# Open_tES.net
KiCad netlist of a schematic drawn in EAGLE
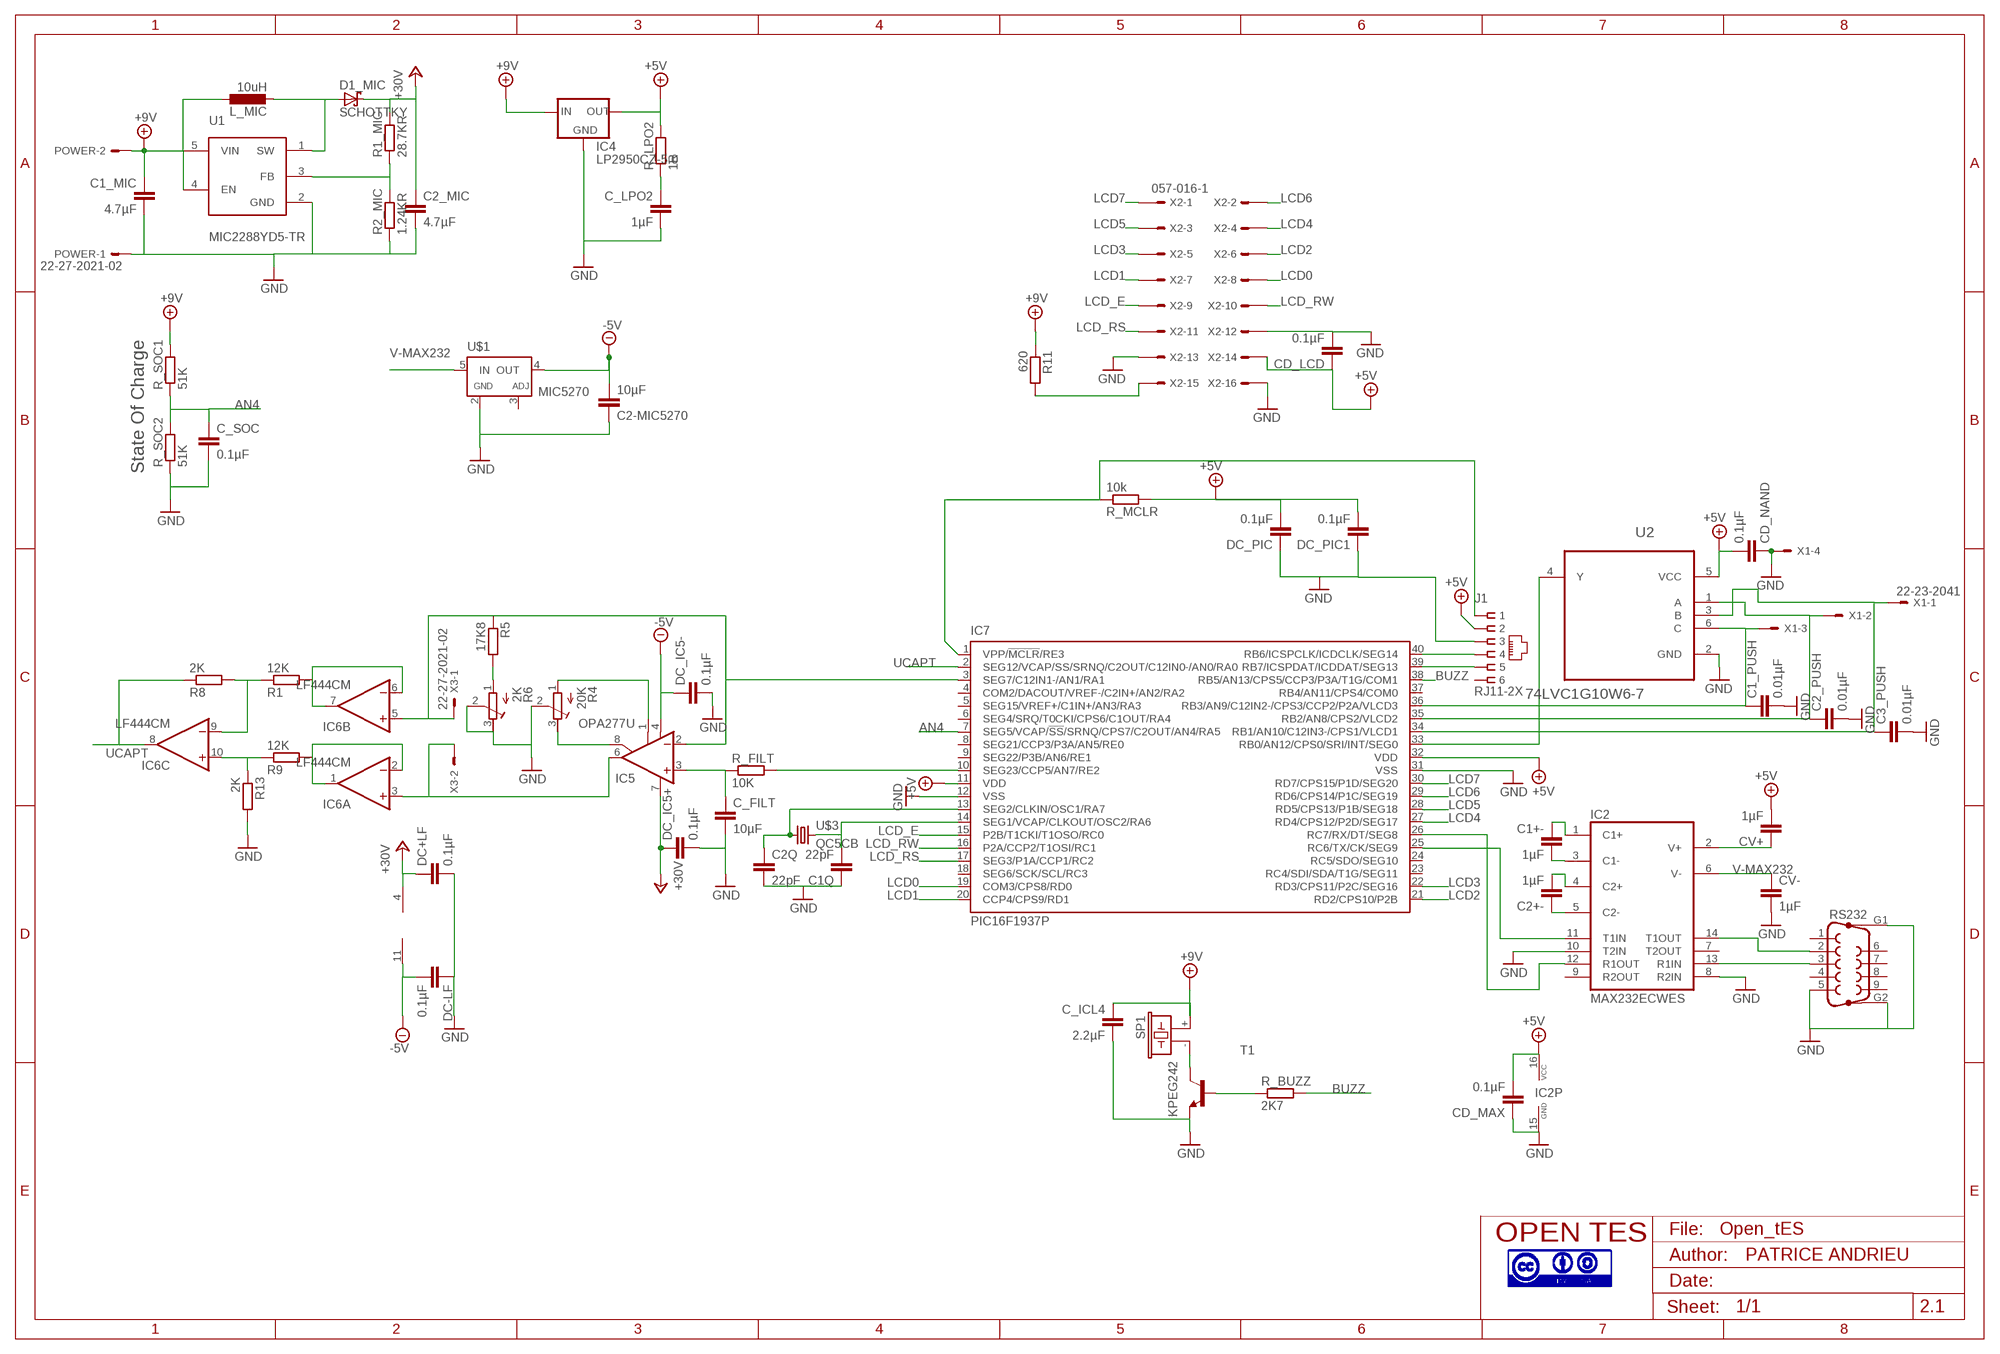
[diagram p0: schematic, sheet 1]

(export (version "E")
  (design (tool "Eeschema 10.0.6"))
  (components
    (comp (ref "C1+-")
      (value "1µF")
      (footprint "eagle-import:C0805")
      (libsource (lib "eagle-import") (part "C-EUC0805"))
    )
    (comp (ref "C1Q")
      (value "22pF")
      (footprint "eagle-import:C0805")
      (libsource (lib "eagle-import") (part "C-EUC0805"))
    )
    (comp (ref "C1_MIC")
      (value "4.7µF")
      (footprint "eagle-import:C0805")
      (libsource (lib "eagle-import") (part "C-EUC0805"))
    )
    (comp (ref "C1_PUSH")
      (value "0.01µF")
      (footprint "eagle-import:C0805")
      (libsource (lib "eagle-import") (part "C-EUC0805"))
    )
    (comp (ref "C2+-")
      (value "1µF")
      (footprint "eagle-import:C0805")
      (libsource (lib "eagle-import") (part "C-EUC0805"))
    )
    (comp (ref "C2-MIC5270")
      (value "10µF")
      (footprint "eagle-import:C0805")
      (libsource (lib "eagle-import") (part "C-EUC0805"))
    )
    (comp (ref "C2Q")
      (value "22pF")
      (footprint "eagle-import:C0805")
      (libsource (lib "eagle-import") (part "C-EUC0805"))
    )
    (comp (ref "C2_MIC")
      (value "4.7µF")
      (footprint "eagle-import:C0805")
      (libsource (lib "eagle-import") (part "C-EUC0805"))
    )
    (comp (ref "C2_PUSH")
      (value "0.01µF")
      (footprint "eagle-import:C0805")
      (libsource (lib "eagle-import") (part "C-EUC0805"))
    )
    (comp (ref "C3_PUSH")
      (value "0.01µF")
      (footprint "eagle-import:C0805")
      (libsource (lib "eagle-import") (part "C-EUC0805"))
    )
    (comp (ref "CD_LCD")
      (value "0.1µF")
      (footprint "eagle-import:C0805")
      (libsource (lib "eagle-import") (part "C-EUC0805"))
    )
    (comp (ref "CD_MAX")
      (value "0.1µF")
      (footprint "eagle-import:C0805")
      (libsource (lib "eagle-import") (part "C-EUC0805"))
    )
    (comp (ref "CD_NAND")
      (value "0.1µF")
      (footprint "eagle-import:C0805")
      (libsource (lib "eagle-import") (part "C-EUC0805"))
    )
    (comp (ref "CV+")
      (value "1µF")
      (footprint "eagle-import:C0805")
      (libsource (lib "eagle-import") (part "C-EUC0805"))
    )
    (comp (ref "CV-")
      (value "1µF")
      (footprint "eagle-import:C0805")
      (libsource (lib "eagle-import") (part "C-EUC0805"))
    )
    (comp (ref "C_FILT")
      (value "10µF")
      (footprint "eagle-import:C0805")
      (libsource (lib "eagle-import") (part "C-EUC0805"))
    )
    (comp (ref "C_ICL4")
      (value "2.2µF")
      (footprint "eagle-import:C0805K")
      (libsource (lib "eagle-import") (part "C-EUC0805K"))
    )
    (comp (ref "C_LPO2")
      (value "1µF")
      (footprint "eagle-import:C0805")
      (libsource (lib "eagle-import") (part "C-EUC0805"))
    )
    (comp (ref "C_SOC")
      (value "0.1µF")
      (footprint "eagle-import:C0805")
      (libsource (lib "eagle-import") (part "C-EUC0805"))
    )
    (comp (ref "D1_MIC")
      (value "SCHOTTKY")
      (footprint "eagle-import:SOD80")
      (libsource (lib "eagle-import") (part "SCHOTTKY"))
    )
    (comp (ref "DC+LF")
      (value "0.1µF")
      (footprint "eagle-import:C0805")
      (libsource (lib "eagle-import") (part "C-EUC0805"))
    )
    (comp (ref "DC-LF")
      (value "0.1µF")
      (footprint "eagle-import:C0805")
      (libsource (lib "eagle-import") (part "C-EUC0805"))
    )
    (comp (ref "DC_IC5+")
      (value "0.1µF")
      (footprint "eagle-import:C0805")
      (libsource (lib "eagle-import") (part "C-EUC0805"))
    )
    (comp (ref "DC_IC5-")
      (value "0.1µF")
      (footprint "eagle-import:C0805")
      (libsource (lib "eagle-import") (part "C-EUC0805"))
    )
    (comp (ref "DC_PIC")
      (value "0.1µF")
      (footprint "eagle-import:C0805")
      (libsource (lib "eagle-import") (part "C-EUC0805"))
    )
    (comp (ref "DC_PIC1")
      (value "0.1µF")
      (footprint "eagle-import:C0805")
      (libsource (lib "eagle-import") (part "C-EUC0805"))
    )
    (comp (ref "IC2")
      (value "MAX232ECWES")
      (footprint "eagle-import:SO16")
      (fields (field (name "OC_FARNELL") "2511968"))
      (libsource (lib "eagle-import") (part "MAX232ECWES"))
    )
    (comp (ref "IC4")
      (value "LP2950CZ-5.0")
      (footprint "eagle-import:TO92")
      (libsource (lib "eagle-import") (part "LP2950?CZ-5.0"))
    )
    (comp (ref "IC5")
      (value "OPA277U")
      (footprint "eagle-import:SO08")
      (libsource (lib "eagle-import") (part "OPA277U"))
    )
    (comp (ref "IC6")
      (value "LF444CM")
      (footprint "eagle-import:SO14")
      (fields (field (name "OC_FARNELL") "1564711"))
      (libsource (lib "eagle-import") (part "LF444CM"))
    )
    (comp (ref "IC7")
      (value "PIC16F1937P")
      (footprint "eagle-import:DIL40")
      (fields (field (name "MPN") "PIC16F1937-I/P"))
      (libsource (lib "eagle-import") (part "PIC16F193?P7"))
    )
    (comp (ref "J1")
      (value "RJ11-2X")
      (footprint "eagle-import:RJ11-NO_SHIELD")
      (fields (field (name "OC_FARNELL") "3363132"))
      (libsource (lib "eagle-import") (part "RJ11-2X"))
    )
    (comp (ref "L_MIC")
      (value "10uH")
      (footprint "eagle-import:L2012C")
      (libsource (lib "eagle-import") (part "L-EUL2012C"))
    )
    (comp (ref "POWER")
      (value "22-27-2021-02")
      (footprint "eagle-import:6410-02")
      (fields (field (name "OC_FARNELL") "9731148+1654528+1462641"))
      (libsource (lib "eagle-import") (part "22-?-0227-2021"))
    )
    (comp (ref "R1")
      (value "12K")
      (footprint "eagle-import:R0805")
      (libsource (lib "eagle-import") (part "R-EU_R0805"))
    )
    (comp (ref "R1_MIC")
      (value "28.7KR")
      (footprint "eagle-import:R0805")
      (libsource (lib "eagle-import") (part "R-EU_R0805"))
    )
    (comp (ref "R2_MIC")
      (value "1.24KR")
      (footprint "eagle-import:R0805")
      (libsource (lib "eagle-import") (part "R-EU_R0805"))
    )
    (comp (ref "R4")
      (value "20K")
      (footprint "eagle-import:RTRIM3214W")
      (libsource (lib "eagle-import") (part "R-TRIMM3214W"))
    )
    (comp (ref "R5")
      (value "17K8")
      (footprint "eagle-import:M0805")
      (libsource (lib "eagle-import") (part "R-EU_M0805"))
    )
    (comp (ref "R6")
      (value "2K")
      (footprint "eagle-import:RTRIM3214W")
      (libsource (lib "eagle-import") (part "R-TRIMM3214W"))
    )
    (comp (ref "R8")
      (value "2K")
      (footprint "eagle-import:R0805")
      (libsource (lib "eagle-import") (part "R-EU_R0805"))
    )
    (comp (ref "R9")
      (value "12K")
      (footprint "eagle-import:R0805")
      (libsource (lib "eagle-import") (part "R-EU_R0805"))
    )
    (comp (ref "R11")
      (value "620")
      (footprint "eagle-import:0204_7")
      (libsource (lib "eagle-import") (part "R-EU_0204/7"))
    )
    (comp (ref "R13")
      (value "2K")
      (footprint "eagle-import:R0805")
      (libsource (lib "eagle-import") (part "R-EU_R0805"))
    )
    (comp (ref "RS232")
      (value "F09HP")
      (footprint "eagle-import:F09HP")
      (fields (field (name "OC_FARNELL") "1084701"))
      (libsource (lib "eagle-import") (part "F09HP"))
    )
    (comp (ref "R_BUZZ")
      (value "2K7")
      (footprint "eagle-import:R0805")
      (libsource (lib "eagle-import") (part "R-EU_R0805"))
    )
    (comp (ref "R_FILT")
      (value "10K")
      (footprint "eagle-import:R0805")
      (libsource (lib "eagle-import") (part "R-EU_R0805"))
    )
    (comp (ref "R_LPO2")
      (value "1R")
      (footprint "eagle-import:R0805")
      (libsource (lib "eagle-import") (part "R-EU_R0805"))
    )
    (comp (ref "R_MCLR")
      (value "10k")
      (footprint "eagle-import:0204_7")
      (libsource (lib "eagle-import") (part "R-EU_0204/7"))
    )
    (comp (ref "R_SOC1")
      (value "51K")
      (footprint "eagle-import:R0805")
      (libsource (lib "eagle-import") (part "R-EU_R0805"))
    )
    (comp (ref "R_SOC2")
      (value "51K")
      (footprint "eagle-import:R0805")
      (libsource (lib "eagle-import") (part "R-EU_R0805"))
    )
    (comp (ref "SP1")
      (value "KPEG242")
      (footprint "eagle-import:KPEG242")
      (fields (field (name "OC_FARNELL") "1502726"))
      (libsource (lib "eagle-import") (part "KPEG242"))
    )
    (comp (ref "T1")
      (value "BFR92-NPN-SOT23-BEC")
      (footprint "eagle-import:SOT23-BEC")
      (libsource (lib "eagle-import") (part "-NPN-SOT23-BECBFR92"))
    )
    (comp (ref "U$1")
      (value "MIC5270")
      (footprint "eagle-import:SOT23-5L")
      (libsource (lib "eagle-import") (part "MIC5270"))
    )
    (comp (ref "U$3")
      (value "QC5CB")
      (footprint "eagle-import:QC5CB")
      (libsource (lib "eagle-import") (part "QC5CB"))
    )
    (comp (ref "U$4")
      (value "FRAME")
      (footprint "eagle-import:OPEN_TE_VERSION")
      (fields (field (name "VERSION") "2.1"))
      (libsource (lib "eagle-import") (part "FRAME"))
    )
    (comp (ref "U1")
      (value "MIC2288YD5-TR")
      (footprint "eagle-import:SOT23-5L")
      (libsource (lib "eagle-import") (part "MIC2288YD5-TR"))
    )
    (comp (ref "U2")
      (value "74LVC1G10W6-7")
      (footprint "eagle-import:SOT95P280X135-6N")
      (libsource (lib "eagle-import") (part "74LVC1G10W6-7"))
    )
    (comp (ref "X1")
      (value "22-23-2041")
      (footprint "eagle-import:22-23-2041")
      (fields (field (name "MF") "MOLEX") (field (name "OC_FARNELL") "1462920+1462809+1462641"))
      (libsource (lib "eagle-import") (part "22-23-2041"))
    )
    (comp (ref "X2")
      (value "057-016-1")
      (footprint "eagle-import:057-016-1")
      (fields (field (name "OC_FARNELL") "1554029"))
      (libsource (lib "eagle-import") (part "057-016-1"))
    )
    (comp (ref "X3")
      (value "22-27-2021-02")
      (footprint "eagle-import:6410-02")
      (fields (field (name "OC_FARNELL") "9731148+1654528+1462641"))
      (libsource (lib "eagle-import") (part "22-?-0227-2021"))
    )
  )
  (nets
    (net (code "1") (name "+5V") (class "Default")
      (node (ref "CD_LCD") (pin "1") (pinfunction "1_1") (pintype "passive"))
      (node (ref "CD_MAX") (pin "2") (pinfunction "2_2") (pintype "passive"))
      (node (ref "CD_NAND") (pin "2") (pinfunction "2_2") (pintype "passive"))
      (node (ref "CV+") (pin "2") (pinfunction "2_2") (pintype "passive"))
      (node (ref "DC_PIC") (pin "2") (pinfunction "2_2") (pintype "passive"))
      (node (ref "DC_PIC1") (pin "2") (pinfunction "2_2") (pintype "passive"))
      (node (ref "IC2") (pin "16") (pinfunction "VCC_16") (pintype "power_in"))
      (node (ref "IC4") (pin "1") (pinfunction "OUT_1") (pintype "passive"))
      (node (ref "IC7") (pin "11") (pinfunction "VDD_11") (pintype "power_in"))
      (node (ref "IC7") (pin "32") (pinfunction "VDD_32") (pintype "power_in"))
      (node (ref "J1") (pin "2") (pinfunction "2_2") (pintype "passive"))
      (node (ref "R_LPO2") (pin "2") (pinfunction "2_2") (pintype "passive"))
      (node (ref "R_MCLR") (pin "2") (pinfunction "2_2") (pintype "passive"))
      (node (ref "U2") (pin "5") (pinfunction "VCC_5") (pintype "power_in"))
      (node (ref "X2") (pin "14") (pinfunction "S_14") (pintype "passive"))
    )
    (net (code "2") (name "+9V") (class "Default")
      (node (ref "C1_MIC") (pin "1") (pinfunction "1_1") (pintype "passive"))
      (node (ref "C_ICL4") (pin "1") (pinfunction "1_1") (pintype "passive"))
      (node (ref "IC4") (pin "3") (pinfunction "IN_3") (pintype "input"))
      (node (ref "L_MIC") (pin "1") (pinfunction "1_1") (pintype "passive"))
      (node (ref "POWER") (pin "2") (pinfunction "S_2") (pintype "passive"))
      (node (ref "R11") (pin "1") (pinfunction "1_1") (pintype "passive"))
      (node (ref "R_SOC1") (pin "2") (pinfunction "2_2") (pintype "passive"))
      (node (ref "SP1") (pin "+") (pinfunction "1_+") (pintype "passive"))
      (node (ref "U1") (pin "4") (pinfunction "EN_4") (pintype "bidirectional"))
      (node (ref "U1") (pin "5") (pinfunction "VIN_5") (pintype "bidirectional"))
    )
    (net (code "3") (name "+30V") (class "Default")
      (node (ref "C2_MIC") (pin "1") (pinfunction "1_1") (pintype "passive"))
      (node (ref "D1_MIC") (pin "C") (pinfunction "C_C") (pintype "passive"))
      (node (ref "DC+LF") (pin "1") (pinfunction "1_1") (pintype "passive"))
      (node (ref "DC_IC5+") (pin "1") (pinfunction "1_1") (pintype "passive"))
      (node (ref "IC5") (pin "7") (pinfunction "V+_7") (pintype "power_in"))
      (node (ref "IC6") (pin "4") (pinfunction "V+_4") (pintype "power_in"))
      (node (ref "R1_MIC") (pin "2") (pinfunction "2_2") (pintype "passive"))
    )
    (net (code "4") (name "-5V") (class "Default")
      (node (ref "C2-MIC5270") (pin "2") (pinfunction "2_2") (pintype "passive"))
      (node (ref "DC-LF") (pin "2") (pinfunction "2_2") (pintype "passive"))
      (node (ref "DC_IC5-") (pin "1") (pinfunction "1_1") (pintype "passive"))
      (node (ref "IC5") (pin "4") (pinfunction "V-_4") (pintype "power_in"))
      (node (ref "IC6") (pin "11") (pinfunction "V-_11") (pintype "power_in"))
      (node (ref "U$1") (pin "4") (pinfunction "OUT_4") (pintype "output"))
    )
    (net (code "5") (name "/AN4") (class "Default")
      (node (ref "C_SOC") (pin "1") (pinfunction "1_1") (pintype "passive"))
      (node (ref "IC7") (pin "7") (pinfunction "SEG5/VCAP/~{SS}/SRNQ/CPS7/C2OUT/AN4/RA5_7") (pintype "bidirectional"))
      (node (ref "R_SOC1") (pin "1") (pinfunction "1_1") (pintype "passive"))
      (node (ref "R_SOC2") (pin "2") (pinfunction "2_2") (pintype "passive"))
    )
    (net (code "6") (name "/BUZZ") (class "Default")
      (node (ref "IC7") (pin "38") (pinfunction "RB5/AN13/CPS5/CCP3/P3A/T1G/COM1_38") (pintype "bidirectional"))
      (node (ref "R_BUZZ") (pin "2") (pinfunction "2_2") (pintype "passive"))
    )
    (net (code "7") (name "/LCD0") (class "Default")
      (node (ref "IC7") (pin "19") (pinfunction "COM3/CPS8/RD0_19") (pintype "bidirectional"))
      (node (ref "X2") (pin "8") (pinfunction "S_8") (pintype "passive"))
    )
    (net (code "8") (name "/LCD1") (class "Default")
      (node (ref "IC7") (pin "20") (pinfunction "CCP4/CPS9/RD1_20") (pintype "bidirectional"))
      (node (ref "X2") (pin "7") (pinfunction "S_7") (pintype "passive"))
    )
    (net (code "9") (name "/LCD2") (class "Default")
      (node (ref "IC7") (pin "21") (pinfunction "RD2/CPS10/P2B_21") (pintype "bidirectional"))
      (node (ref "X2") (pin "6") (pinfunction "S_6") (pintype "passive"))
    )
    (net (code "10") (name "/LCD3") (class "Default")
      (node (ref "IC7") (pin "22") (pinfunction "RD3/CPS11/P2C/SEG16_22") (pintype "bidirectional"))
      (node (ref "X2") (pin "5") (pinfunction "S_5") (pintype "passive"))
    )
    (net (code "11") (name "/LCD4") (class "Default")
      (node (ref "IC7") (pin "27") (pinfunction "RD4/CPS12/P2D/SEG17_27") (pintype "bidirectional"))
      (node (ref "X2") (pin "4") (pinfunction "S_4") (pintype "passive"))
    )
    (net (code "12") (name "/LCD5") (class "Default")
      (node (ref "IC7") (pin "28") (pinfunction "RD5/CPS13/P1B/SEG18_28") (pintype "bidirectional"))
      (node (ref "X2") (pin "3") (pinfunction "S_3") (pintype "passive"))
    )
    (net (code "13") (name "/LCD6") (class "Default")
      (node (ref "IC7") (pin "29") (pinfunction "RD6/CPS14/P1C/SEG19_29") (pintype "bidirectional"))
      (node (ref "X2") (pin "2") (pinfunction "S_2") (pintype "passive"))
    )
    (net (code "14") (name "/LCD7") (class "Default")
      (node (ref "IC7") (pin "30") (pinfunction "RD7/CPS15/P1D/SEG20_30") (pintype "bidirectional"))
      (node (ref "X2") (pin "1") (pinfunction "S_1") (pintype "passive"))
    )
    (net (code "15") (name "/LCD_E") (class "Default")
      (node (ref "IC7") (pin "15") (pinfunction "P2B/T1CKI/T1OSO/RC0_15") (pintype "bidirectional"))
      (node (ref "X2") (pin "9") (pinfunction "S_9") (pintype "passive"))
    )
    (net (code "16") (name "/LCD_RS") (class "Default")
      (node (ref "IC7") (pin "17") (pinfunction "SEG3/P1A/CCP1/RC2_17") (pintype "bidirectional"))
      (node (ref "X2") (pin "11") (pinfunction "S_11") (pintype "passive"))
    )
    (net (code "17") (name "/LCD_RW") (class "Default")
      (node (ref "IC7") (pin "16") (pinfunction "P2A/CCP2/T1OSI/RC1_16") (pintype "bidirectional"))
      (node (ref "X2") (pin "10") (pinfunction "S_10") (pintype "passive"))
    )
    (net (code "18") (name "/UCAPT") (class "Default")
      (node (ref "IC6") (pin "8") (pinfunction "OUT_8") (pintype "output"))
      (node (ref "IC7") (pin "2") (pinfunction "SEG12/VCAP/SS/SRNQ/C2OUT/C12IN0-/AN0/RA0_2") (pintype "bidirectional"))
      (node (ref "R8") (pin "1") (pinfunction "1_1") (pintype "passive"))
    )
    (net (code "19") (name "/V-MAX232") (class "Default")
      (node (ref "CV-") (pin "1") (pinfunction "1_1") (pintype "passive"))
      (node (ref "IC2") (pin "6") (pinfunction "V-_6") (pintype "bidirectional"))
      (node (ref "U$1") (pin "5") (pinfunction "IN_5") (pintype "input"))
    )
    (net (code "20") (name "GND") (class "Default")
      (node (ref "C1Q") (pin "1") (pinfunction "1_1") (pintype "passive"))
      (node (ref "C1_MIC") (pin "2") (pinfunction "2_2") (pintype "passive"))
      (node (ref "C1_PUSH") (pin "2") (pinfunction "2_2") (pintype "passive"))
      (node (ref "C2-MIC5270") (pin "1") (pinfunction "1_1") (pintype "passive"))
      (node (ref "C2Q") (pin "2") (pinfunction "2_2") (pintype "passive"))
      (node (ref "C2_MIC") (pin "2") (pinfunction "2_2") (pintype "passive"))
      (node (ref "C2_PUSH") (pin "2") (pinfunction "2_2") (pintype "passive"))
      (node (ref "C3_PUSH") (pin "2") (pinfunction "2_2") (pintype "passive"))
      (node (ref "CD_LCD") (pin "2") (pinfunction "2_2") (pintype "passive"))
      (node (ref "CD_MAX") (pin "1") (pinfunction "1_1") (pintype "passive"))
      (node (ref "CD_NAND") (pin "1") (pinfunction "1_1") (pintype "passive"))
      (node (ref "CV-") (pin "2") (pinfunction "2_2") (pintype "passive"))
      (node (ref "C_FILT") (pin "2") (pinfunction "2_2") (pintype "passive"))
      (node (ref "C_ICL4") (pin "2") (pinfunction "2_2") (pintype "passive"))
      (node (ref "C_LPO2") (pin "2") (pinfunction "2_2") (pintype "passive"))
      (node (ref "C_SOC") (pin "2") (pinfunction "2_2") (pintype "passive"))
      (node (ref "DC+LF") (pin "2") (pinfunction "2_2") (pintype "passive"))
      (node (ref "DC-LF") (pin "1") (pinfunction "1_1") (pintype "passive"))
      (node (ref "DC_IC5+") (pin "2") (pinfunction "2_2") (pintype "passive"))
      (node (ref "DC_IC5-") (pin "2") (pinfunction "2_2") (pintype "passive"))
      (node (ref "DC_PIC") (pin "1") (pinfunction "1_1") (pintype "passive"))
      (node (ref "DC_PIC1") (pin "1") (pinfunction "1_1") (pintype "passive"))
      (node (ref "IC2") (pin "10") (pinfunction "T2IN_10") (pintype "input"))
      (node (ref "IC2") (pin "15") (pinfunction "GND_15") (pintype "power_in"))
      (node (ref "IC2") (pin "8") (pinfunction "R2IN_8") (pintype "input"))
      (node (ref "IC4") (pin "2") (pinfunction "GND_2") (pintype "input"))
      (node (ref "IC7") (pin "12") (pinfunction "VSS_12") (pintype "power_in"))
      (node (ref "IC7") (pin "31") (pinfunction "VSS_31") (pintype "power_in"))
      (node (ref "J1") (pin "3") (pinfunction "3_3") (pintype "passive"))
      (node (ref "POWER") (pin "1") (pinfunction "S_1") (pintype "passive"))
      (node (ref "R13") (pin "2") (pinfunction "2_2") (pintype "passive"))
      (node (ref "R2_MIC") (pin "1") (pinfunction "1_1") (pintype "passive"))
      (node (ref "R4") (pin "2") (pinfunction "S_2") (pintype "passive"))
      (node (ref "R6") (pin "2") (pinfunction "S_2") (pintype "passive"))
      (node (ref "R6") (pin "3") (pinfunction "E_3") (pintype "passive"))
      (node (ref "RS232") (pin "5") (pinfunction "5_5") (pintype "passive"))
      (node (ref "RS232") (pin "G1") (pinfunction "G1_G1") (pintype "passive"))
      (node (ref "RS232") (pin "G2") (pinfunction "G2_G2") (pintype "passive"))
      (node (ref "R_SOC2") (pin "1") (pinfunction "1_1") (pintype "passive"))
      (node (ref "T1") (pin "E") (pinfunction "E_E") (pintype "passive"))
      (node (ref "U$1") (pin "2") (pinfunction "GND_2") (pintype "power_in"))
      (node (ref "U1") (pin "2") (pinfunction "GND_2") (pintype "bidirectional"))
      (node (ref "U2") (pin "2") (pinfunction "GND_2") (pintype "passive"))
      (node (ref "X1") (pin "4") (pinfunction "S_4") (pintype "passive"))
      (node (ref "X2") (pin "12") (pinfunction "S_12") (pintype "passive"))
      (node (ref "X2") (pin "13") (pinfunction "S_13") (pintype "passive"))
      (node (ref "X2") (pin "16") (pinfunction "S_16") (pintype "passive"))
    )
    (net (code "21") (name "Net-(C_LPO2-Pad1)") (class "Default")
      (node (ref "C_LPO2") (pin "1") (pinfunction "1_1") (pintype "passive"))
      (node (ref "R_LPO2") (pin "1") (pinfunction "1_1") (pintype "passive"))
    )
    (net (code "22") (name "Net-(IC2A-C1+)") (class "Default")
      (node (ref "C1+-") (pin "1") (pinfunction "1_1") (pintype "passive"))
      (node (ref "IC2") (pin "1") (pinfunction "C1+_1") (pintype "bidirectional"))
    )
    (net (code "23") (name "Net-(IC2A-C1-)") (class "Default")
      (node (ref "C1+-") (pin "2") (pinfunction "2_2") (pintype "passive"))
      (node (ref "IC2") (pin "3") (pinfunction "C1-_3") (pintype "bidirectional"))
    )
    (net (code "24") (name "Net-(IC2A-C2+)") (class "Default")
      (node (ref "C2+-") (pin "2") (pinfunction "2_2") (pintype "passive"))
      (node (ref "IC2") (pin "4") (pinfunction "C2+_4") (pintype "bidirectional"))
    )
    (net (code "25") (name "Net-(IC2A-C2-)") (class "Default")
      (node (ref "C2+-") (pin "1") (pinfunction "1_1") (pintype "passive"))
      (node (ref "IC2") (pin "5") (pinfunction "C2-_5") (pintype "bidirectional"))
    )
    (net (code "26") (name "Net-(IC2A-R1IN)") (class "Default")
      (node (ref "IC2") (pin "13") (pinfunction "R1IN_13") (pintype "input"))
      (node (ref "RS232") (pin "3") (pinfunction "3_3") (pintype "passive"))
    )
    (net (code "27") (name "Net-(IC2A-R1OUT)") (class "Default")
      (node (ref "IC2") (pin "12") (pinfunction "R1OUT_12") (pintype "output"))
      (node (ref "IC7") (pin "26") (pinfunction "RC7/RX/DT/SEG8_26") (pintype "bidirectional"))
    )
    (net (code "28") (name "Net-(IC2A-T1IN)") (class "Default")
      (node (ref "IC2") (pin "11") (pinfunction "T1IN_11") (pintype "input"))
      (node (ref "IC7") (pin "25") (pinfunction "RC6/TX/CK/SEG9_25") (pintype "bidirectional"))
    )
    (net (code "29") (name "Net-(IC2A-T1OUT)") (class "Default")
      (node (ref "IC2") (pin "14") (pinfunction "T1OUT_14") (pintype "output"))
      (node (ref "RS232") (pin "2") (pinfunction "2_2") (pintype "passive"))
    )
    (net (code "30") (name "Net-(IC2A-V+)") (class "Default")
      (node (ref "CV+") (pin "1") (pinfunction "1_1") (pintype "passive"))
      (node (ref "IC2") (pin "2") (pinfunction "V+_2") (pintype "bidirectional"))
    )
    (net (code "31") (name "Net-(IC5-+IN)") (class "Default")
      (node (ref "C_FILT") (pin "1") (pinfunction "1_1") (pintype "passive"))
      (node (ref "IC5") (pin "3") (pinfunction "+IN_3") (pintype "input"))
      (node (ref "R_FILT") (pin "1") (pinfunction "1_1") (pintype "passive"))
    )
    (net (code "32") (name "Net-(IC5--IN)") (class "Default")
      (node (ref "IC5") (pin "2") (pinfunction "-IN_2") (pintype "input"))
      (node (ref "IC6") (pin "5") (pinfunction "+IN_5") (pintype "input"))
      (node (ref "IC7") (pin "3") (pinfunction "SEG7/C12IN1-/AN1/RA1_3") (pintype "bidirectional"))
      (node (ref "R5") (pin "1") (pinfunction "1_1") (pintype "passive"))
      (node (ref "X3") (pin "1") (pinfunction "S_1") (pintype "passive"))
    )
    (net (code "33") (name "Net-(IC5-CMP1)") (class "Default")
      (node (ref "IC5") (pin "1") (pinfunction "CMP1_1") (pintype "passive"))
      (node (ref "R4") (pin "1") (pinfunction "A_1") (pintype "passive"))
    )
    (net (code "34") (name "Net-(IC5-CMP2)") (class "Default")
      (node (ref "IC5") (pin "8") (pinfunction "CMP2_8") (pintype "passive"))
      (node (ref "R4") (pin "3") (pinfunction "E_3") (pintype "passive"))
    )
    (net (code "35") (name "Net-(IC5-OUT)") (class "Default")
      (node (ref "IC5") (pin "6") (pinfunction "OUT_6") (pintype "output"))
      (node (ref "IC6") (pin "3") (pinfunction "+IN_3") (pintype "input"))
      (node (ref "X3") (pin "2") (pinfunction "S_2") (pintype "passive"))
    )
    (net (code "36") (name "Net-(IC6A--IN)") (class "Default")
      (node (ref "IC6") (pin "1") (pinfunction "OUT_1") (pintype "output"))
      (node (ref "IC6") (pin "2") (pinfunction "-IN_2") (pintype "input"))
      (node (ref "R9") (pin "2") (pinfunction "2_2") (pintype "passive"))
    )
    (net (code "37") (name "Net-(IC6B--IN)") (class "Default")
      (node (ref "IC6") (pin "6") (pinfunction "-IN_6") (pintype "input"))
      (node (ref "IC6") (pin "7") (pinfunction "OUT_7") (pintype "output"))
      (node (ref "R1") (pin "2") (pinfunction "2_2") (pintype "passive"))
    )
    (net (code "38") (name "Net-(IC6C-+IN)") (class "Default")
      (node (ref "IC6") (pin "10") (pinfunction "+IN_10") (pintype "input"))
      (node (ref "R13") (pin "1") (pinfunction "1_1") (pintype "passive"))
      (node (ref "R9") (pin "1") (pinfunction "1_1") (pintype "passive"))
    )
    (net (code "39") (name "Net-(IC6C--IN)") (class "Default")
      (node (ref "IC6") (pin "9") (pinfunction "-IN_9") (pintype "input"))
      (node (ref "R1") (pin "1") (pinfunction "1_1") (pintype "passive"))
      (node (ref "R8") (pin "2") (pinfunction "2_2") (pintype "passive"))
    )
    (net (code "40") (name "Net-(IC7-RB0{slash}AN12{slash}CPS0{slash}SRI{slash}INT{slash}SEG0)") (class "Default")
      (node (ref "IC7") (pin "33") (pinfunction "RB0/AN12/CPS0/SRI/INT/SEG0_33") (pintype "bidirectional"))
      (node (ref "U2") (pin "4") (pinfunction "Y_4") (pintype "output"))
    )
    (net (code "41") (name "Net-(IC7-RB1{slash}AN10{slash}C12IN3-{slash}CPS1{slash}VLCD1)") (class "Default")
      (node (ref "C3_PUSH") (pin "1") (pinfunction "1_1") (pintype "passive"))
      (node (ref "IC7") (pin "34") (pinfunction "RB1/AN10/C12IN3-/CPS1/VLCD1_34") (pintype "bidirectional"))
      (node (ref "U2") (pin "3") (pinfunction "B_3") (pintype "input"))
      (node (ref "X1") (pin "1") (pinfunction "S_1") (pintype "passive"))
    )
    (net (code "42") (name "Net-(IC7-RB2{slash}AN8{slash}CPS2{slash}VLCD2)") (class "Default")
      (node (ref "C2_PUSH") (pin "1") (pinfunction "1_1") (pintype "passive"))
      (node (ref "IC7") (pin "35") (pinfunction "RB2/AN8/CPS2/VLCD2_35") (pintype "bidirectional"))
      (node (ref "U2") (pin "1") (pinfunction "A_1") (pintype "input"))
      (node (ref "X1") (pin "2") (pinfunction "S_2") (pintype "passive"))
    )
    (net (code "43") (name "Net-(IC7-RB3{slash}AN9{slash}C12IN2-{slash}CPS3{slash}CCP2{slash}P2A{slash}VLCD3)") (class "Default")
      (node (ref "C1_PUSH") (pin "1") (pinfunction "1_1") (pintype "passive"))
      (node (ref "IC7") (pin "36") (pinfunction "RB3/AN9/C12IN2-/CPS3/CCP2/P2A/VLCD3_36") (pintype "bidirectional"))
      (node (ref "U2") (pin "6") (pinfunction "C_6") (pintype "input"))
      (node (ref "X1") (pin "3") (pinfunction "S_3") (pintype "passive"))
    )
    (net (code "44") (name "Net-(IC7-RB6{slash}ICSPCLK{slash}ICDCLK{slash}SEG14)") (class "Default")
      (node (ref "IC7") (pin "40") (pinfunction "RB6/ICSPCLK/ICDCLK/SEG14_40") (pintype "bidirectional"))
      (node (ref "J1") (pin "4") (pinfunction "4_4") (pintype "passive"))
    )
    (net (code "45") (name "Net-(IC7-RB7{slash}ICSPDAT{slash}ICDDAT{slash}SEG13)") (class "Default")
      (node (ref "IC7") (pin "39") (pinfunction "RB7/ICSPDAT/ICDDAT/SEG13_39") (pintype "bidirectional"))
      (node (ref "J1") (pin "5") (pinfunction "5_5") (pintype "passive"))
    )
    (net (code "46") (name "Net-(IC7-SEG1{slash}VCAP{slash}CLKOUT{slash}OSC2{slash}RA6)") (class "Default")
      (node (ref "C1Q") (pin "2") (pinfunction "2_2") (pintype "passive"))
      (node (ref "IC7") (pin "14") (pinfunction "SEG1/VCAP/CLKOUT/OSC2/RA6_14") (pintype "bidirectional"))
      (node (ref "U$3") (pin "2") (pinfunction "2_2") (pintype "passive"))
    )
    (net (code "47") (name "Net-(IC7-SEG2{slash}CLKIN{slash}OSC1{slash}RA7)") (class "Default")
      (node (ref "C2Q") (pin "1") (pinfunction "1_1") (pintype "passive"))
      (node (ref "IC7") (pin "13") (pinfunction "SEG2/CLKIN/OSC1/RA7_13") (pintype "bidirectional"))
      (node (ref "U$3") (pin "1") (pinfunction "1_1") (pintype "passive"))
    )
    (net (code "48") (name "Net-(IC7-SEG23{slash}CCP5{slash}AN7{slash}RE2)") (class "Default")
      (node (ref "IC7") (pin "10") (pinfunction "SEG23/CCP5/AN7/RE2_10") (pintype "bidirectional"))
      (node (ref "R_FILT") (pin "2") (pinfunction "2_2") (pintype "passive"))
    )
    (net (code "49") (name "Net-(IC7-VPP{slash}~{MCLR}{slash}RE3)") (class "Default")
      (node (ref "IC7") (pin "1") (pinfunction "VPP/~{MCLR}/RE3_1") (pintype "input"))
      (node (ref "J1") (pin "1") (pinfunction "1_1") (pintype "passive"))
      (node (ref "R_MCLR") (pin "1") (pinfunction "1_1") (pintype "passive"))
    )
    (net (code "50") (name "Net-(R6-A)") (class "Default")
      (node (ref "R5") (pin "2") (pinfunction "2_2") (pintype "passive"))
      (node (ref "R6") (pin "1") (pinfunction "A_1") (pintype "passive"))
    )
    (net (code "51") (name "Net-(R_BUZZ-Pad1)") (class "Default")
      (node (ref "R_BUZZ") (pin "1") (pinfunction "1_1") (pintype "passive"))
      (node (ref "T1") (pin "B") (pinfunction "B_B") (pintype "passive"))
    )
    (net (code "52") (name "Net-(SP1-2)") (class "Default")
      (node (ref "SP1") (pin "-") (pinfunction "2_-") (pintype "passive"))
      (node (ref "T1") (pin "C") (pinfunction "C_C") (pintype "passive"))
    )
    (net (code "53") (name "Net-(U1-FB)") (class "Default")
      (node (ref "R1_MIC") (pin "1") (pinfunction "1_1") (pintype "passive"))
      (node (ref "R2_MIC") (pin "2") (pinfunction "2_2") (pintype "passive"))
      (node (ref "U1") (pin "3") (pinfunction "FB_3") (pintype "bidirectional"))
    )
    (net (code "54") (name "Net-(U1-SW)") (class "Default")
      (node (ref "D1_MIC") (pin "A") (pinfunction "A_A") (pintype "passive"))
      (node (ref "L_MIC") (pin "2") (pinfunction "2_2") (pintype "passive"))
      (node (ref "U1") (pin "1") (pinfunction "SW_1") (pintype "bidirectional"))
    )
    (net (code "55") (name "Net-(X2G-S)") (class "Default")
      (node (ref "R11") (pin "2") (pinfunction "2_2") (pintype "passive"))
      (node (ref "X2") (pin "15") (pinfunction "S_15") (pintype "passive"))
    )
    (net (code "56") (name "unconnected-(IC2A-R2OUT-Pad9)") (class "Default")
      (node (ref "IC2") (pin "9") (pinfunction "R2OUT_9") (pintype "output"))
    )
    (net (code "57") (name "unconnected-(IC2A-T2OUT-Pad7)") (class "Default")
      (node (ref "IC2") (pin "7") (pinfunction "T2OUT_7") (pintype "output"))
    )
    (net (code "58") (name "unconnected-(IC7-COM2{slash}DACOUT{slash}VREF-{slash}C2IN+{slash}AN2{slash}RA2-Pad4)") (class "Default")
      (node (ref "IC7") (pin "4") (pinfunction "COM2/DACOUT/VREF-/C2IN+/AN2/RA2_4") (pintype "bidirectional"))
    )
    (net (code "59") (name "unconnected-(IC7-RB4{slash}AN11{slash}CPS4{slash}COM0-Pad37)") (class "Default")
      (node (ref "IC7") (pin "37") (pinfunction "RB4/AN11/CPS4/COM0_37") (pintype "bidirectional"))
    )
    (net (code "60") (name "unconnected-(IC7-RC4{slash}SDI{slash}SDA{slash}T1G{slash}SEG11-Pad23)") (class "Default")
      (node (ref "IC7") (pin "23") (pinfunction "RC4/SDI/SDA/T1G/SEG11_23") (pintype "bidirectional"))
    )
    (net (code "61") (name "unconnected-(IC7-RC5{slash}SDO{slash}SEG10-Pad24)") (class "Default")
      (node (ref "IC7") (pin "24") (pinfunction "RC5/SDO/SEG10_24") (pintype "bidirectional"))
    )
    (net (code "62") (name "unconnected-(IC7-SEG4{slash}SRQ{slash}T0CKI{slash}CPS6{slash}C1OUT{slash}RA4-Pad6)") (class "Default")
      (node (ref "IC7") (pin "6") (pinfunction "SEG4/SRQ/T0CKI/CPS6/C1OUT/RA4_6") (pintype "bidirectional"))
    )
    (net (code "63") (name "unconnected-(IC7-SEG6{slash}SCK{slash}SCL{slash}RC3-Pad18)") (class "Default")
      (node (ref "IC7") (pin "18") (pinfunction "SEG6/SCK/SCL/RC3_18") (pintype "bidirectional"))
    )
    (net (code "64") (name "unconnected-(IC7-SEG15{slash}VREF+{slash}C1IN+{slash}AN3{slash}RA3-Pad5)") (class "Default")
      (node (ref "IC7") (pin "5") (pinfunction "SEG15/VREF+/C1IN+/AN3/RA3_5") (pintype "bidirectional"))
    )
    (net (code "65") (name "unconnected-(IC7-SEG21{slash}CCP3{slash}P3A{slash}AN5{slash}RE0-Pad8)") (class "Default")
      (node (ref "IC7") (pin "8") (pinfunction "SEG21/CCP3/P3A/AN5/RE0_8") (pintype "bidirectional"))
    )
    (net (code "66") (name "unconnected-(IC7-SEG22{slash}P3B{slash}AN6{slash}RE1-Pad9)") (class "Default")
      (node (ref "IC7") (pin "9") (pinfunction "SEG22/P3B/AN6/RE1_9") (pintype "bidirectional"))
    )
    (net (code "67") (name "unconnected-(J1-Pad6)") (class "Default")
      (node (ref "J1") (pin "6") (pinfunction "6_6") (pintype "passive"))
    )
    (net (code "68") (name "unconnected-(RS232-Pad1)") (class "Default")
      (node (ref "RS232") (pin "1") (pinfunction "1_1") (pintype "passive"))
    )
    (net (code "69") (name "unconnected-(RS232-Pad4)") (class "Default")
      (node (ref "RS232") (pin "4") (pinfunction "4_4") (pintype "passive"))
    )
    (net (code "70") (name "unconnected-(RS232-Pad6)") (class "Default")
      (node (ref "RS232") (pin "6") (pinfunction "6_6") (pintype "passive"))
    )
    (net (code "71") (name "unconnected-(RS232-Pad7)") (class "Default")
      (node (ref "RS232") (pin "7") (pinfunction "7_7") (pintype "passive"))
    )
    (net (code "72") (name "unconnected-(RS232-Pad8)") (class "Default")
      (node (ref "RS232") (pin "8") (pinfunction "8_8") (pintype "passive"))
    )
    (net (code "73") (name "unconnected-(RS232-Pad9)") (class "Default")
      (node (ref "RS232") (pin "9") (pinfunction "9_9") (pintype "passive"))
    )
    (net (code "74") (name "unconnected-(U$1-ADJ-Pad3)") (class "Default")
      (node (ref "U$1") (pin "3") (pinfunction "ADJ_3") (pintype "passive"))
    )
  )
)
